# 1.net
KiCad netlist of a schematic drawn in Altium Designer
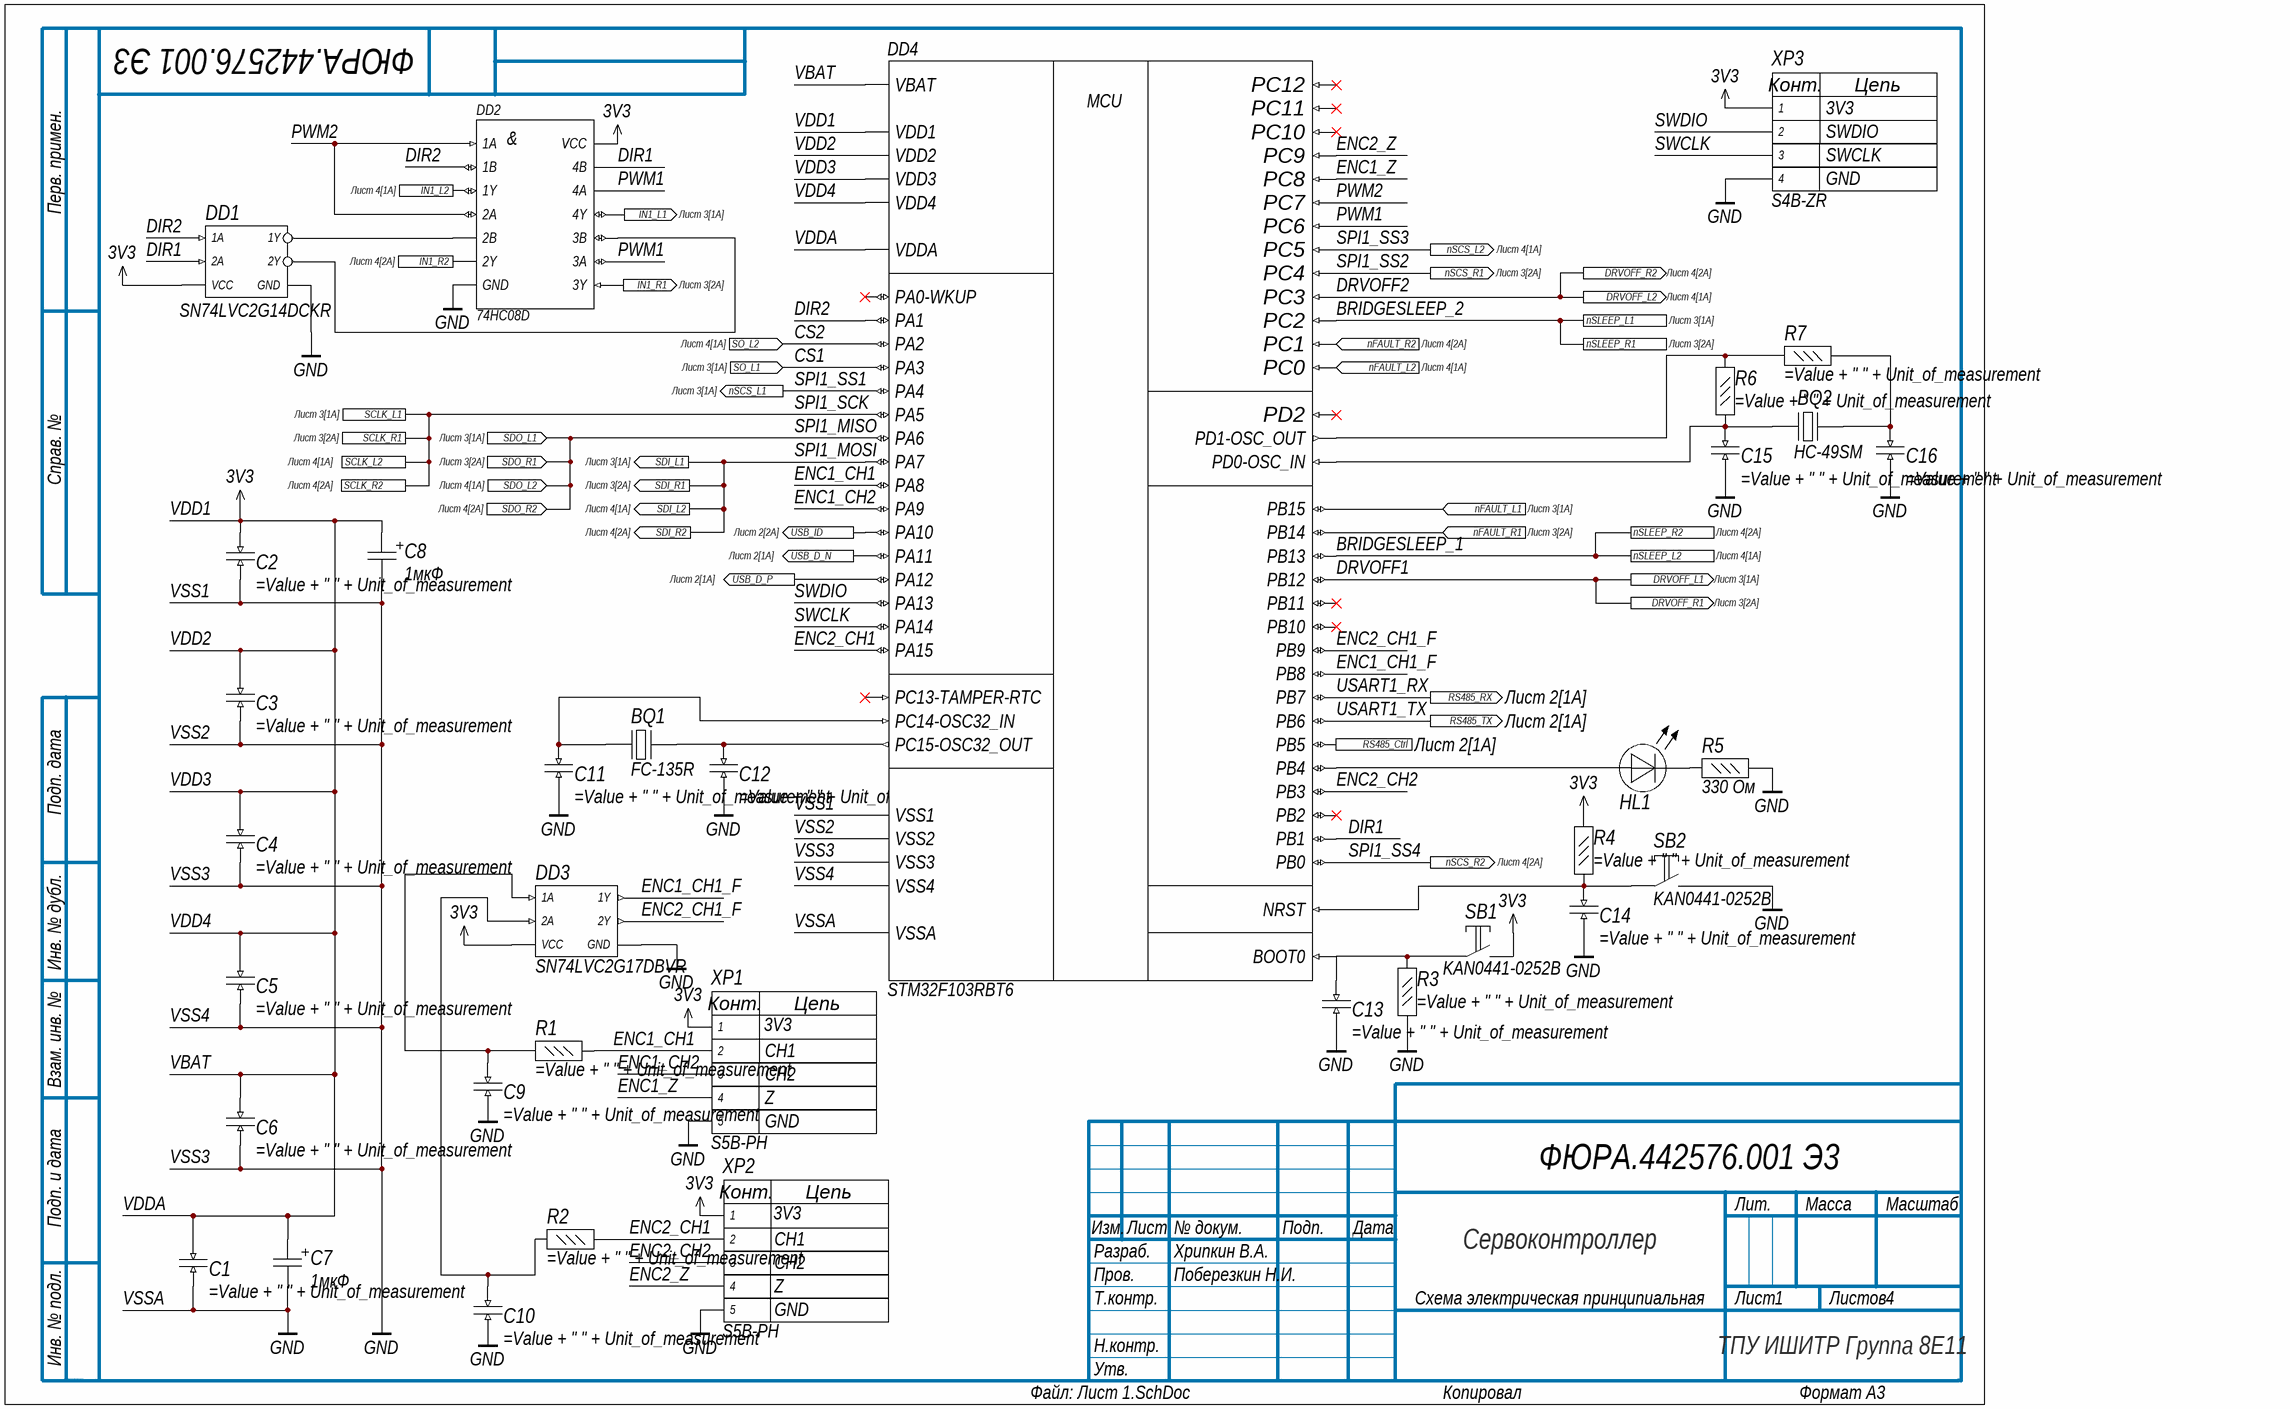
[diagram p0: Лист 1.SchDoc]

(export (version "E")
  (design (tool "Eeschema 10.0.6"))
  (components
    (comp (ref "BQ1")
      (value "FC-135R")
      (footprint "FC-135R")
      (description "Кварцевый резонатор 32,768 кГц; SMD")
      (libsource (lib "Complicated") (part "FC-135R"))
    )
    (comp (ref "BQ2")
      (value "HC-49SM")
      (footprint "HC-49SM")
      (description "Кварцевый резонатор 8 МГц; SMD")
      (libsource (lib "Complicated") (part "HC-49SM"))
    )
    (comp (ref "C1")
      (value "100нФ")
      (footprint "CAP_0603")
      (description "Конденсатор керамический, типоразмера 0603")
      (libsource (lib "PassiveComponents") (part "CAP_0603"))
    )
    (comp (ref "C2")
      (value "100нФ")
      (footprint "CAP_0603")
      (description "Конденсатор керамический, типоразмера 0603")
      (libsource (lib "PassiveComponents") (part "CAP_0603"))
    )
    (comp (ref "C3")
      (value "100нФ")
      (footprint "CAP_0603")
      (description "Конденсатор керамический, типоразмера 0603")
      (libsource (lib "PassiveComponents") (part "CAP_0603"))
    )
    (comp (ref "C4")
      (value "100нФ")
      (footprint "CAP_0603")
      (description "Конденсатор керамический, типоразмера 0603")
      (libsource (lib "PassiveComponents") (part "CAP_0603"))
    )
    (comp (ref "C5")
      (value "100нФ")
      (footprint "CAP_0603")
      (description "Конденсатор керамический, типоразмера 0603")
      (libsource (lib "PassiveComponents") (part "CAP_0603"))
    )
    (comp (ref "C6")
      (value "100нФ")
      (footprint "CAP_0603")
      (description "Конденсатор керамический, типоразмера 0603")
      (libsource (lib "PassiveComponents") (part "CAP_0603"))
    )
    (comp (ref "C7")
      (value "1мкФ")
      (footprint "TECAP_A")
      (description "Описание свойств компонента")
      (libsource (lib "PassiveComponents") (part "TECAP_A"))
    )
    (comp (ref "C8")
      (value "1мкФ")
      (footprint "TECAP_A")
      (description "Описание свойств компонента")
      (libsource (lib "PassiveComponents") (part "TECAP_A"))
    )
    (comp (ref "C9")
      (value "10пФ")
      (footprint "CAP_0603")
      (description "Конденсатор керамический, типоразмера 0603")
      (libsource (lib "PassiveComponents") (part "CAP_0603"))
    )
    (comp (ref "C10")
      (value "10пФ")
      (footprint "CAP_0603")
      (description "Конденсатор керамический, типоразмера 0603")
      (libsource (lib "PassiveComponents") (part "CAP_0603"))
    )
    (comp (ref "C11")
      (value "20пФ")
      (footprint "CAP_0603")
      (description "Конденсатор керамический, типоразмера 0603")
      (libsource (lib "PassiveComponents") (part "CAP_0603"))
    )
    (comp (ref "C12")
      (value "20пФ")
      (footprint "CAP_0603")
      (description "Конденсатор керамический, типоразмера 0603")
      (libsource (lib "PassiveComponents") (part "CAP_0603"))
    )
    (comp (ref "C13")
      (value "100нФ")
      (footprint "CAP_0603")
      (description "Конденсатор керамический, типоразмера 0603")
      (libsource (lib "PassiveComponents") (part "CAP_0603"))
    )
    (comp (ref "C14")
      (value "100нФ")
      (footprint "CAP_0603")
      (description "Конденсатор керамический, типоразмера 0603")
      (libsource (lib "PassiveComponents") (part "CAP_0603"))
    )
    (comp (ref "C15")
      (value "20пФ")
      (footprint "CAP_0603")
      (description "Конденсатор керамический, типоразмера 0603")
      (libsource (lib "PassiveComponents") (part "CAP_0603"))
    )
    (comp (ref "C16")
      (value "20пФ")
      (footprint "CAP_0603")
      (description "Конденсатор керамический, типоразмера 0603")
      (libsource (lib "PassiveComponents") (part "CAP_0603"))
    )
    (comp (ref "DD1")
      (value "SN74LVC2G14DCKR")
      (footprint "SOT363 (SC70-6)")
      (description "Сдвоенный инвертор с триггером Шмидта")
      (libsource (lib "ICs") (part "SN74LVC2G14DCKR"))
    )
    (comp (ref "DD2")
      (value "74HC08D")
      (footprint "SO14")
      (description "Логическая ИС, QUAD 2-INPUT AND GATE")
      (libsource (lib "ICs") (part "74HC08D"))
    )
    (comp (ref "DD3")
      (value "SN74LVC2G17DBVR")
      (footprint "SOT23-6")
      (description "Сдвоенный буфер с триггером Шмитта на входе")
      (libsource (lib "ICs") (part "SN74LVC2G17DBVR"))
    )
    (comp (ref "DD4")
      (value "STM32F103RBT6")
      (footprint "LQFP-64")
      (description "Микроконтроллер 32-Бит, Cortex-M3, 72МГц, 128КБ Flash, USB, CAN [LQFP-64]")
      (libsource (lib "ICs") (part "STM32F103RBT6"))
    )
    (comp (ref "HL1") (value "3") (footprint "LED_0805") (libsource (lib "Complicated") (part "LED_0805_O")))
    (comp (ref "R1")
      (value "100кОм")
      (footprint "RES_0603")
      (description "Резистор, типоразмера 0603")
      (libsource (lib "SimpleComponents") (part "RES_0603"))
    )
    (comp (ref "R2")
      (value "100кОм")
      (footprint "RES_0603")
      (description "Резистор, типоразмера 0603")
      (libsource (lib "SimpleComponents") (part "RES_0603"))
    )
    (comp (ref "R3")
      (value "10кОм")
      (footprint "RES_0603")
      (description "Резистор, типоразмера 0603")
      (libsource (lib "") (part "RES_0603_1"))
    )
    (comp (ref "R4")
      (value "10кОм")
      (footprint "RES_0603")
      (description "Резистор, типоразмера 0603")
      (libsource (lib "") (part "RES_0603_2"))
    )
    (comp (ref "R5")
      (value "330 Ом")
      (footprint "RES_0603")
      (description "Резистор, типоразмера 0603")
      (libsource (lib "SimpleComponents") (part "RES_0603"))
    )
    (comp (ref "R6")
      (value "1МОм")
      (footprint "RES_0603")
      (description "Резистор, типоразмера 0603")
      (libsource (lib "") (part "RES_0603_2"))
    )
    (comp (ref "R7")
      (value "100кОм")
      (footprint "RES_0603")
      (description "Резистор, типоразмера 0603")
      (libsource (lib "SimpleComponents") (part "RES_0603"))
    )
    (comp (ref "SB1")
      (value "KAN0441-0252B")
      (footprint "SMD-BUTTON_6x3.5")
      (description "Описание свойств компонента")
      (libsource (lib "PassiveComponents") (part "SMD-Button_6x3.5"))
    )
    (comp (ref "SB2")
      (value "KAN0441-0252B")
      (footprint "SMD-BUTTON_6x3.5")
      (description "Описание свойств компонента")
      (libsource (lib "PassiveComponents") (part "SMD-Button_6x3.5"))
    )
    (comp (ref "XP1")
      (value "S5B-PH")
      (footprint "S5B-PH-K-S")
      (description "JST PH 5pin 2 mm pitch; horizontal; through hole OR full smd; S5B-PH-SM4-TB")
      (libsource (lib "SimpleComponents") (part "S5B-PH"))
    )
    (comp (ref "XP2")
      (value "S5B-PH")
      (footprint "S5B-PH-K-S")
      (description "JST PH 5pin 2 mm pitch; horizontal; through hole OR full smd; S5B-PH-SM4-TB")
      (libsource (lib "SimpleComponents") (part "S5B-PH"))
    )
    (comp (ref "XP3")
      (value "S4B-ZR")
      (footprint "S4B-ZR-SM4A-TF")
      (description "JST ZH 4pin 1.5 mm pitch; horizontal; through hole OR full smd; S4B-ZR")
      (libsource (lib "PassiveComponents") (part "S4B-ZR"))
    )
  )
  (nets
    (net (code "1") (name "/BRIDGESLEEP_1") (class "Default")
      (node (ref "DD4") (pin "34") (pinfunction "PB13_34") (pintype "bidirectional"))
    )
    (net (code "2") (name "/BRIDGESLEEP_2") (class "Default")
      (node (ref "DD4") (pin "10") (pinfunction "PC2_10") (pintype "input"))
    )
    (net (code "3") (name "/CS1") (class "Default")
      (node (ref "DD4") (pin "17") (pinfunction "PA3_17") (pintype "bidirectional"))
    )
    (net (code "4") (name "/CS2") (class "Default")
      (node (ref "DD4") (pin "16") (pinfunction "PA2_16") (pintype "bidirectional"))
    )
    (net (code "5") (name "/DIR1") (class "Default")
      (node (ref "DD1") (pin "3") (pinfunction "2A_3") (pintype "input"))
      (node (ref "DD2") (pin "13") (pinfunction "4B_13") (pintype "power_in"))
      (node (ref "DD4") (pin "27") (pinfunction "PB1_27") (pintype "bidirectional"))
    )
    (net (code "6") (name "/DIR2") (class "Default")
      (node (ref "DD1") (pin "1") (pinfunction "1A_1") (pintype "input"))
      (node (ref "DD2") (pin "2") (pinfunction "1B_2") (pintype "bidirectional"))
      (node (ref "DD4") (pin "15") (pinfunction "PA1_15") (pintype "bidirectional"))
    )
    (net (code "7") (name "/DRVOFF1") (class "Default")
      (node (ref "DD4") (pin "33") (pinfunction "PB12_33") (pintype "bidirectional"))
    )
    (net (code "8") (name "/DRVOFF2") (class "Default")
      (node (ref "DD4") (pin "11") (pinfunction "PC3_11") (pintype "input"))
    )
    (net (code "9") (name "/ENC1_CH1") (class "Default")
      (node (ref "DD4") (pin "41") (pinfunction "PA8_41") (pintype "bidirectional"))
      (node (ref "R1") (pin "2") (pinfunction "2_2") (pintype "passive"))
      (node (ref "XP1") (pin "2") (pinfunction "2_2") (pintype "passive"))
    )
    (net (code "10") (name "/ENC1_CH1_F") (class "Default")
      (node (ref "DD3") (pin "6") (pinfunction "1Y_6") (pintype "output"))
      (node (ref "DD4") (pin "61") (pinfunction "PB8_61") (pintype "bidirectional"))
    )
    (net (code "11") (name "/ENC1_CH2") (class "Default")
      (node (ref "DD4") (pin "42") (pinfunction "PA9_42") (pintype "bidirectional"))
      (node (ref "XP1") (pin "3") (pinfunction "3_3") (pintype "passive"))
    )
    (net (code "12") (name "/ENC1_Z") (class "Default")
      (node (ref "DD4") (pin "39") (pinfunction "PC8_39") (pintype "input"))
      (node (ref "XP1") (pin "4") (pinfunction "4_4") (pintype "passive"))
    )
    (net (code "13") (name "/ENC2_CH1") (class "Default")
      (node (ref "DD4") (pin "50") (pinfunction "PA15_50") (pintype "bidirectional"))
      (node (ref "R2") (pin "2") (pinfunction "2_2") (pintype "passive"))
      (node (ref "XP2") (pin "2") (pinfunction "2_2") (pintype "passive"))
    )
    (net (code "14") (name "/ENC2_CH1_F") (class "Default")
      (node (ref "DD3") (pin "4") (pinfunction "2Y_4") (pintype "output"))
      (node (ref "DD4") (pin "62") (pinfunction "PB9_62") (pintype "bidirectional"))
    )
    (net (code "15") (name "/ENC2_CH2") (class "Default")
      (node (ref "DD4") (pin "55") (pinfunction "PB3_55") (pintype "bidirectional"))
      (node (ref "XP2") (pin "3") (pinfunction "3_3") (pintype "passive"))
    )
    (net (code "16") (name "/ENC2_Z") (class "Default")
      (node (ref "DD4") (pin "40") (pinfunction "PC9_40") (pintype "input"))
      (node (ref "XP2") (pin "4") (pinfunction "4_4") (pintype "passive"))
    )
    (net (code "17") (name "/IN1_L1") (class "Default")
      (node (ref "DD2") (pin "11") (pinfunction "4Y_11") (pintype "bidirectional"))
    )
    (net (code "18") (name "/IN1_L2") (class "Default")
      (node (ref "DD2") (pin "3") (pinfunction "1Y_3") (pintype "bidirectional"))
    )
    (net (code "19") (name "/IN1_R1") (class "Default")
      (node (ref "DD2") (pin "8") (pinfunction "3Y_8") (pintype "input"))
    )
    (net (code "20") (name "/IN1_R2") (class "Default")
      (node (ref "DD2") (pin "6") (pinfunction "2Y_6") (pintype "power_in"))
    )
    (net (code "21") (name "/PWM1") (class "Default")
      (node (ref "DD2") (pin "12") (pinfunction "4A_12") (pintype "power_in"))
      (node (ref "DD2") (pin "9") (pinfunction "3A_9") (pintype "bidirectional"))
      (node (ref "DD4") (pin "37") (pinfunction "PC6_37") (pintype "input"))
    )
    (net (code "22") (name "/PWM2") (class "Default")
      (node (ref "DD2") (pin "1") (pinfunction "1A_1") (pintype "input"))
      (node (ref "DD2") (pin "4") (pinfunction "2A_4") (pintype "bidirectional"))
      (node (ref "DD4") (pin "38") (pinfunction "PC7_38") (pintype "input"))
    )
    (net (code "23") (name "/RS485_Ctrl") (class "Default")
      (node (ref "DD4") (pin "57") (pinfunction "PB5_57") (pintype "bidirectional"))
    )
    (net (code "24") (name "/SPI1_MISO") (class "Default")
      (node (ref "DD4") (pin "22") (pinfunction "PA6_22") (pintype "bidirectional"))
    )
    (net (code "25") (name "/SPI1_MOSI") (class "Default")
      (node (ref "DD4") (pin "23") (pinfunction "PA7_23") (pintype "bidirectional"))
    )
    (net (code "26") (name "/SPI1_SCK") (class "Default")
      (node (ref "DD4") (pin "21") (pinfunction "PA5_21") (pintype "bidirectional"))
    )
    (net (code "27") (name "/SPI1_SS1") (class "Default")
      (node (ref "DD4") (pin "20") (pinfunction "PA4_20") (pintype "bidirectional"))
    )
    (net (code "28") (name "/SPI1_SS2") (class "Default")
      (node (ref "DD4") (pin "24") (pinfunction "PC4_24") (pintype "input"))
    )
    (net (code "29") (name "/SPI1_SS3") (class "Default")
      (node (ref "DD4") (pin "25") (pinfunction "PC5_25") (pintype "input"))
    )
    (net (code "30") (name "/SPI1_SS4") (class "Default")
      (node (ref "DD4") (pin "26") (pinfunction "PB0_26") (pintype "bidirectional"))
    )
    (net (code "31") (name "/SWCLK") (class "Default")
      (node (ref "DD4") (pin "49") (pinfunction "PA14_49") (pintype "bidirectional"))
      (node (ref "XP3") (pin "3") (pinfunction "3_3") (pintype "passive"))
    )
    (net (code "32") (name "/SWDIO") (class "Default")
      (node (ref "DD4") (pin "46") (pinfunction "PA13_46") (pintype "bidirectional"))
      (node (ref "XP3") (pin "2") (pinfunction "2_2") (pintype "passive"))
    )
    (net (code "33") (name "/USART1_RX") (class "Default")
      (node (ref "DD4") (pin "59") (pinfunction "PB7_59") (pintype "bidirectional"))
    )
    (net (code "34") (name "/USART1_TX") (class "Default")
      (node (ref "DD4") (pin "58") (pinfunction "PB6_58") (pintype "bidirectional"))
    )
    (net (code "35") (name "/USB_D_N") (class "Default")
      (node (ref "DD4") (pin "44") (pinfunction "PA11_44") (pintype "bidirectional"))
    )
    (net (code "36") (name "/USB_D_P") (class "Default")
      (node (ref "DD4") (pin "45") (pinfunction "PA12_45") (pintype "bidirectional"))
    )
    (net (code "37") (name "/USB_ID") (class "Default")
      (node (ref "DD4") (pin "43") (pinfunction "PA10_43") (pintype "bidirectional"))
    )
    (net (code "38") (name "/nFAULT_L1") (class "Default")
      (node (ref "DD4") (pin "36") (pinfunction "PB15_36") (pintype "bidirectional"))
    )
    (net (code "39") (name "/nFAULT_L2") (class "Default")
      (node (ref "DD4") (pin "8") (pinfunction "PC0_8") (pintype "input"))
    )
    (net (code "40") (name "/nFAULT_R1") (class "Default")
      (node (ref "DD4") (pin "35") (pinfunction "PB14_35") (pintype "bidirectional"))
    )
    (net (code "41") (name "/nFAULT_R2") (class "Default")
      (node (ref "DD4") (pin "9") (pinfunction "PC1_9") (pintype "input"))
    )
    (net (code "42") (name "3V3") (class "Default")
      (node (ref "C1") (pin "2") (pintype "input"))
      (node (ref "C2") (pin "2") (pintype "input"))
      (node (ref "C3") (pin "2") (pintype "input"))
      (node (ref "C4") (pin "2") (pintype "input"))
      (node (ref "C5") (pin "2") (pintype "input"))
      (node (ref "C6") (pin "2") (pintype "input"))
      (node (ref "C7") (pin "1") (pintype "passive"))
      (node (ref "C8") (pin "1") (pintype "passive"))
      (node (ref "DD1") (pin "5") (pinfunction "VCC_5") (pintype "power_in"))
      (node (ref "DD2") (pin "14") (pinfunction "VCC_14") (pintype "power_in"))
      (node (ref "DD3") (pin "5") (pinfunction "VCC_5") (pintype "power_in"))
      (node (ref "DD4") (pin "1") (pinfunction "VBAT_1") (pintype "power_in"))
      (node (ref "DD4") (pin "13") (pinfunction "VDDA_13") (pintype "power_in"))
      (node (ref "DD4") (pin "19") (pinfunction "VDD1_19") (pintype "power_in"))
      (node (ref "DD4") (pin "32") (pinfunction "VDD2_32") (pintype "power_in"))
      (node (ref "DD4") (pin "48") (pinfunction "VDD3_48") (pintype "power_in"))
      (node (ref "DD4") (pin "64") (pinfunction "VDD4_64") (pintype "power_in"))
      (node (ref "R4") (pin "2") (pinfunction "2_2") (pintype "passive"))
      (node (ref "SB1") (pin "2") (pinfunction "S2_2") (pintype "passive"))
      (node (ref "XP1") (pin "1") (pinfunction "1_1") (pintype "passive"))
      (node (ref "XP2") (pin "1") (pinfunction "1_1") (pintype "passive"))
      (node (ref "XP3") (pin "1") (pinfunction "1_1") (pintype "passive"))
    )
    (net (code "43") (name "GND") (class "Default")
      (node (ref "C1") (pin "1") (pintype "input"))
      (node (ref "C10") (pin "1") (pintype "input"))
      (node (ref "C11") (pin "1") (pintype "input"))
      (node (ref "C12") (pin "1") (pintype "input"))
      (node (ref "C13") (pin "1") (pintype "input"))
      (node (ref "C14") (pin "1") (pintype "input"))
      (node (ref "C15") (pin "1") (pintype "input"))
      (node (ref "C16") (pin "1") (pintype "input"))
      (node (ref "C2") (pin "1") (pintype "input"))
      (node (ref "C3") (pin "1") (pintype "input"))
      (node (ref "C4") (pin "1") (pintype "input"))
      (node (ref "C5") (pin "1") (pintype "input"))
      (node (ref "C6") (pin "1") (pintype "input"))
      (node (ref "C7") (pin "2") (pintype "passive"))
      (node (ref "C8") (pin "2") (pintype "passive"))
      (node (ref "C9") (pin "1") (pintype "input"))
      (node (ref "DD1") (pin "2") (pinfunction "GND_2") (pintype "power_in"))
      (node (ref "DD2") (pin "7") (pinfunction "GND_7") (pintype "power_in"))
      (node (ref "DD3") (pin "2") (pinfunction "GND_2") (pintype "power_in"))
      (node (ref "DD4") (pin "12") (pinfunction "VSSA_12") (pintype "power_in"))
      (node (ref "DD4") (pin "18") (pinfunction "VSS1_18") (pintype "power_in"))
      (node (ref "DD4") (pin "31") (pinfunction "VSS2_31") (pintype "power_in"))
      (node (ref "DD4") (pin "47") (pinfunction "VSS3_47") (pintype "power_in"))
      (node (ref "DD4") (pin "63") (pinfunction "VSS4_63") (pintype "power_in"))
      (node (ref "R3") (pin "2") (pinfunction "2_2") (pintype "passive"))
      (node (ref "R5") (pin "2") (pinfunction "2_2") (pintype "passive"))
      (node (ref "SB2") (pin "2") (pinfunction "S2_2") (pintype "passive"))
      (node (ref "XP1") (pin "5") (pinfunction "5_5") (pintype "passive"))
      (node (ref "XP2") (pin "5") (pinfunction "5_5") (pintype "passive"))
      (node (ref "XP3") (pin "4") (pinfunction "4_4") (pintype "passive"))
    )
    (net (code "44") (name "Net-(BQ2-Pad2)") (class "Default")
      (node (ref "BQ2") (pin "2") (pintype "passive"))
      (node (ref "C16") (pin "2") (pintype "input"))
      (node (ref "R7") (pin "2") (pinfunction "2_2") (pintype "passive"))
    )
    (net (code "45") (name "Net-(DD1-1Y)") (class "Default")
      (node (ref "DD1") (pin "6") (pinfunction "1Y_6") (pintype "output"))
      (node (ref "DD2") (pin "5") (pinfunction "2B_5") (pintype "power_in"))
    )
    (net (code "46") (name "Net-(DD1-2Y)") (class "Default")
      (node (ref "DD1") (pin "4") (pinfunction "2Y_4") (pintype "output"))
      (node (ref "DD2") (pin "10") (pinfunction "3B_10") (pintype "bidirectional"))
    )
    (net (code "47") (name "Net-(DD3-1A)") (class "Default")
      (node (ref "C9") (pin "2") (pintype "input"))
      (node (ref "DD3") (pin "1") (pinfunction "1A_1") (pintype "input"))
      (node (ref "R1") (pin "1") (pinfunction "1_1") (pintype "passive"))
    )
    (net (code "48") (name "Net-(DD3-2A)") (class "Default")
      (node (ref "C10") (pin "2") (pintype "input"))
      (node (ref "DD3") (pin "3") (pinfunction "2A_3") (pintype "input"))
      (node (ref "R2") (pin "1") (pinfunction "1_1") (pintype "passive"))
    )
    (net (code "49") (name "Net-(DD4-BOOT0)") (class "Default")
      (node (ref "C13") (pin "2") (pintype "input"))
      (node (ref "DD4") (pin "60") (pinfunction "BOOT0_60") (pintype "input"))
      (node (ref "R3") (pin "1") (pinfunction "1_1") (pintype "passive"))
      (node (ref "SB1") (pin "1") (pinfunction "S1_1") (pintype "passive"))
    )
    (net (code "50") (name "Net-(DD4-NRST)") (class "Default")
      (node (ref "C14") (pin "2") (pintype "input"))
      (node (ref "DD4") (pin "7") (pinfunction "NRST_7") (pintype "input"))
      (node (ref "R4") (pin "1") (pinfunction "1_1") (pintype "passive"))
      (node (ref "SB2") (pin "1") (pinfunction "S1_1") (pintype "passive"))
    )
    (net (code "51") (name "Net-(DD4-PB4)") (class "Default")
      (node (ref "DD4") (pin "56") (pinfunction "PB4_56") (pintype "bidirectional"))
      (node (ref "HL1") (pin "A") (pinfunction "2_A") (pintype "passive"))
    )
    (net (code "52") (name "Net-(DD4-PC14-OSC32_IN)") (class "Default")
      (node (ref "BQ1") (pin "1") (pintype "passive"))
      (node (ref "C11") (pin "2") (pintype "input"))
      (node (ref "DD4") (pin "3") (pinfunction "PC14-OSC32_IN_3") (pintype "input"))
    )
    (net (code "53") (name "Net-(DD4-PC15-OSC32_OUT)") (class "Default")
      (node (ref "BQ1") (pin "2") (pintype "passive"))
      (node (ref "C12") (pin "2") (pintype "input"))
      (node (ref "DD4") (pin "4") (pinfunction "PC15-OSC32_OUT_4") (pintype "output"))
    )
    (net (code "54") (name "Net-(DD4-PD0-OSC_IN)") (class "Default")
      (node (ref "BQ2") (pin "1") (pintype "passive"))
      (node (ref "C15") (pin "2") (pintype "input"))
      (node (ref "DD4") (pin "5") (pinfunction "PD0-OSC_IN_5") (pintype "input"))
      (node (ref "R6") (pin "1") (pinfunction "1_1") (pintype "passive"))
    )
    (net (code "55") (name "Net-(DD4-PD1-OSC_OUT)") (class "Default")
      (node (ref "DD4") (pin "6") (pinfunction "PD1-OSC_OUT_6") (pintype "output"))
      (node (ref "R6") (pin "2") (pinfunction "2_2") (pintype "passive"))
      (node (ref "R7") (pin "1") (pinfunction "1_1") (pintype "passive"))
    )
    (net (code "56") (name "Net-(HL1-1)") (class "Default")
      (node (ref "HL1") (pin "C") (pinfunction "1_C") (pintype "passive"))
      (node (ref "R5") (pin "1") (pinfunction "1_1") (pintype "passive"))
    )
    (net (code "57") (name "unconnected-(DD4-PA0-WKUP-Pad14)") (class "Default")
      (node (ref "DD4") (pin "14") (pinfunction "PA0-WKUP_14") (pintype "bidirectional+no_connect"))
    )
    (net (code "58") (name "unconnected-(DD4-PB2-Pad28)") (class "Default")
      (node (ref "DD4") (pin "28") (pinfunction "PB2_28") (pintype "bidirectional+no_connect"))
    )
    (net (code "59") (name "unconnected-(DD4-PB10-Pad29)") (class "Default")
      (node (ref "DD4") (pin "29") (pinfunction "PB10_29") (pintype "bidirectional+no_connect"))
    )
    (net (code "60") (name "unconnected-(DD4-PB11-Pad30)") (class "Default")
      (node (ref "DD4") (pin "30") (pinfunction "PB11_30") (pintype "bidirectional+no_connect"))
    )
    (net (code "61") (name "unconnected-(DD4-PC10-Pad51)") (class "Default")
      (node (ref "DD4") (pin "51") (pinfunction "PC10_51") (pintype "input+no_connect"))
    )
    (net (code "62") (name "unconnected-(DD4-PC11-Pad52)") (class "Default")
      (node (ref "DD4") (pin "52") (pinfunction "PC11_52") (pintype "input+no_connect"))
    )
    (net (code "63") (name "unconnected-(DD4-PC12-Pad53)") (class "Default")
      (node (ref "DD4") (pin "53") (pinfunction "PC12_53") (pintype "input+no_connect"))
    )
    (net (code "64") (name "unconnected-(DD4-PC13-TAMPER-RTC-Pad2)") (class "Default")
      (node (ref "DD4") (pin "2") (pinfunction "PC13-TAMPER-RTC_2") (pintype "input+no_connect"))
    )
    (net (code "65") (name "unconnected-(DD4-PD2-Pad54)") (class "Default")
      (node (ref "DD4") (pin "54") (pinfunction "PD2_54") (pintype "input+no_connect"))
    )
  )
)
